# Switches_UI.net
KiCad netlist of a schematic drawn in Altium Designer
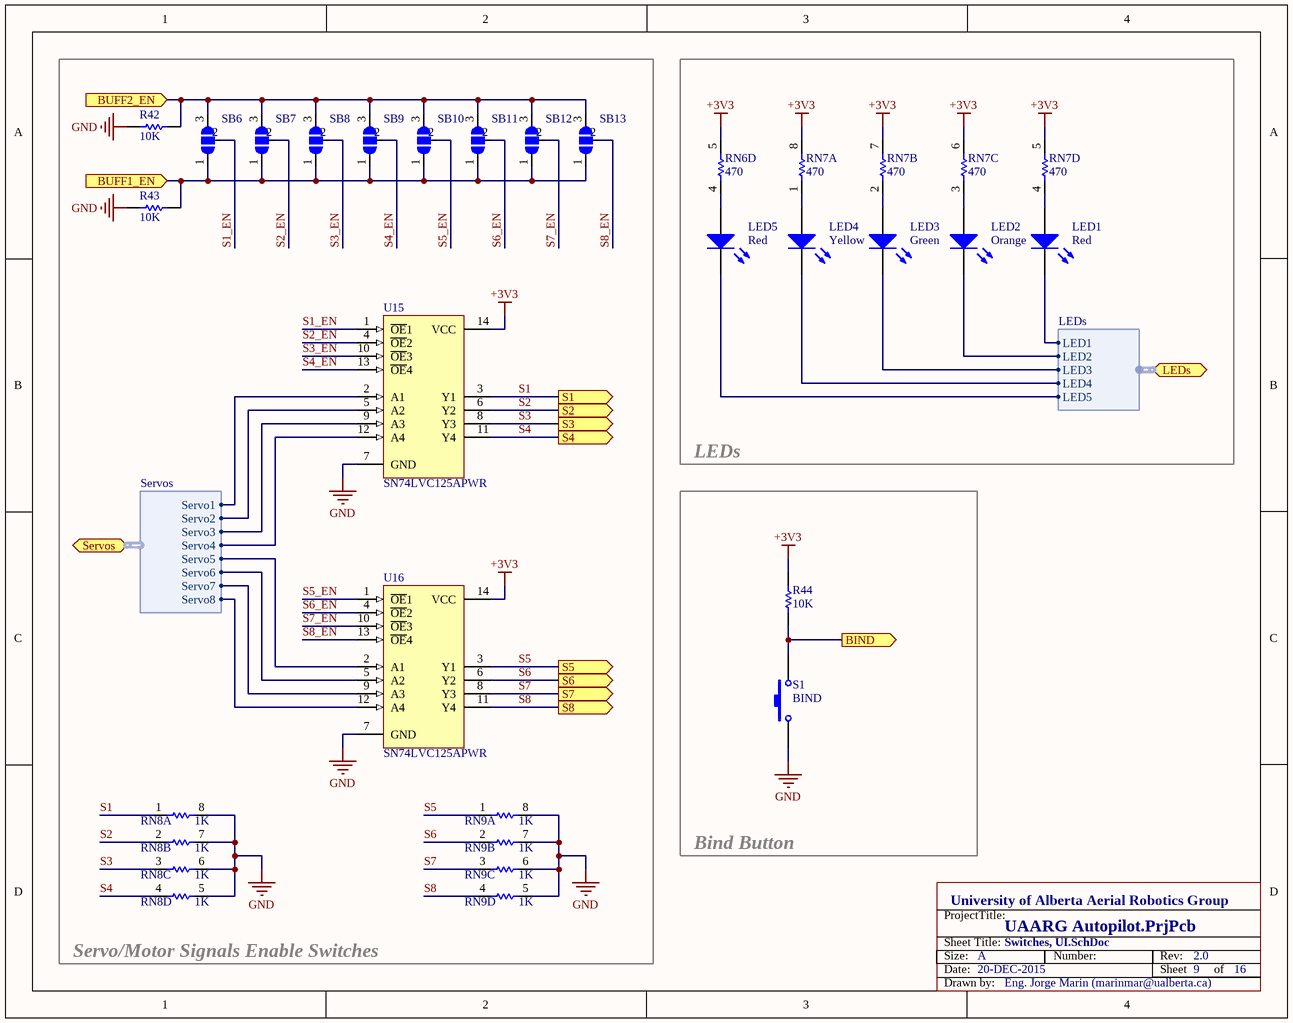
[diagram p0: Switches, UI.SchDoc]

(export (version "E")
  (design (tool "Eeschema 10.0.6"))
  (components
    (comp (ref "LED1")
      (value "LED")
      (footprint "LED_0603[1608M]")
      (description "LED RED CLEAR 0603 SMD")
      (fields
        (field (name "MANUFACTURER") "Lite-On Inc.")
        (field (name "MANUFACTURER PART NUMBER") "LTST-C190KRKT")
        (field (name "COLOR") "Red")
      )
      (libsource (lib "UAARG Autopilot") (part "LED"))
    )
    (comp (ref "LED2")
      (value "LED")
      (footprint "LED_0603[1608M]")
      (description "LED ORANGE CLEAR 0603 SMD")
      (fields
        (field (name "MANUFACTURER") "Lite-On Inc.")
        (field (name "MANUFACTURER PART NUMBER") "LTST-C190AKT")
        (field (name "COLOR") "Orange")
      )
      (libsource (lib "UAARG Autopilot") (part "LED"))
    )
    (comp (ref "LED3")
      (value "LED")
      (footprint "LED_0603[1608M]")
      (description "LED GREEN CLEAR 0603 SMD")
      (fields
        (field (name "MANUFACTURER") "Lite-On Inc.")
        (field (name "MANUFACTURER PART NUMBER") "LTST-C190KGKT")
        (field (name "COLOR") "Green")
      )
      (libsource (lib "UAARG Autopilot") (part "LED"))
    )
    (comp (ref "LED4")
      (value "LED")
      (footprint "LED_0603[1608M]")
      (description "LED YELLOW CLEAR 0603 SMD")
      (fields
        (field (name "MANUFACTURER") "Lite-On Inc.")
        (field (name "MANUFACTURER PART NUMBER") "LTST-C190YKT")
        (field (name "COLOR") "Yellow")
      )
      (libsource (lib "UAARG Autopilot") (part "LED"))
    )
    (comp (ref "LED5")
      (value "LED")
      (footprint "LED_0603[1608M]")
      (description "LED RED CLEAR 0603 SMD")
      (fields
        (field (name "MANUFACTURER") "Lite-On Inc.")
        (field (name "MANUFACTURER PART NUMBER") "LTST-C190KRKT")
        (field (name "COLOR") "Red")
      )
      (libsource (lib "UAARG Autopilot") (part "LED"))
    )
    (comp (ref "R42")
      (value "10K")
      (footprint "RES_0402[1005M]")
      (description "Resistor")
      (fields
        (field (name "MANUFACTURER") "Yageo")
        (field (name "MANUFACTURER PART NUMBER") "RC0402FR-0710KL")
      )
      (libsource (lib "UAARG Autopilot") (part "RES"))
    )
    (comp (ref "R43")
      (value "10K")
      (footprint "RES_0402[1005M]")
      (description "Resistor")
      (fields
        (field (name "MANUFACTURER") "Yageo")
        (field (name "MANUFACTURER PART NUMBER") "RC0402FR-0710KL")
      )
      (libsource (lib "UAARG Autopilot") (part "RES"))
    )
    (comp (ref "R44")
      (value "10K")
      (footprint "RES_0402[1005M]")
      (description "Resistor")
      (fields
        (field (name "MANUFACTURER") "Yageo")
        (field (name "MANUFACTURER PART NUMBER") "RC0402FR-0710KL")
      )
      (libsource (lib "UAARG Autopilot") (part "RES"))
    )
    (comp (ref "RN6")
      (value "470")
      (footprint "RES ARRAY SMD")
      (description "Isolated Resistor Network")
      (fields
        (field (name "MANUFACTURER") "Yageo")
        (field (name "MANUFACTURER PART NUMBER") "YC164-JR-07470RL")
      )
      (libsource (lib "UAARG Autopilot") (part "Res Network 1"))
    )
    (comp (ref "RN7")
      (value "470")
      (footprint "RES ARRAY SMD")
      (description "Isolated Resistor Network")
      (fields
        (field (name "MANUFACTURER") "Yageo")
        (field (name "MANUFACTURER PART NUMBER") "YC164-JR-07470RL")
      )
      (libsource (lib "UAARG Autopilot") (part "Res Network 1"))
    )
    (comp (ref "RN8")
      (value "1K")
      (footprint "RES ARRAY SMD")
      (description "Isolated Resistor Network")
      (fields
        (field (name "MANUFACTURER PART NUMBER") "YC164-JR-071KL")
        (field (name "MANUFACTURER") "Yageo")
      )
      (libsource (lib "UAARG Autopilot") (part "Res Network 1"))
    )
    (comp (ref "RN9")
      (value "1K")
      (footprint "RES ARRAY SMD")
      (description "Isolated Resistor Network")
      (fields
        (field (name "MANUFACTURER PART NUMBER") "YC164-JR-071KL")
        (field (name "MANUFACTURER") "Yageo")
      )
      (libsource (lib "UAARG Autopilot") (part "Res Network 1"))
    )
    (comp (ref "S1")
      (value "BIND")
      (footprint "SMD TACTILE SW KMR 2")
      (description "SWITCH TACTILE SPST-NO 0.05A 32V")
      (fields
        (field (name "MANUFACTURER PART NUMBER") "KMR221GLFS")
        (field (name "MANUFACTURER") "C&K Components")
      )
      (libsource (lib "Miscellaneous Devices") (part "SW-PB"))
    )
    (comp (ref "SB6")
      (value "SMD Jumper 1")
      (footprint "SMD JUMPER 1")
      (description "SMD Jumper 3 positions. Open")
      (libsource (lib "UAARG Autopilot") (part "SMD Jumper 1"))
    )
    (comp (ref "SB7")
      (value "SMD Jumper 1")
      (footprint "SMD JUMPER 1")
      (description "SMD Jumper 3 positions. Open")
      (libsource (lib "UAARG Autopilot") (part "SMD Jumper 1"))
    )
    (comp (ref "SB8")
      (value "SMD Jumper 1")
      (footprint "SMD JUMPER 1")
      (description "SMD Jumper 3 positions. Open")
      (libsource (lib "UAARG Autopilot") (part "SMD Jumper 1"))
    )
    (comp (ref "SB9")
      (value "SMD Jumper 1")
      (footprint "SMD JUMPER 1")
      (description "SMD Jumper 3 positions. Open")
      (libsource (lib "UAARG Autopilot") (part "SMD Jumper 1"))
    )
    (comp (ref "SB10")
      (value "SMD Jumper 1")
      (footprint "SMD JUMPER 1")
      (description "SMD Jumper 3 positions. Open")
      (libsource (lib "UAARG Autopilot") (part "SMD Jumper 1"))
    )
    (comp (ref "SB11")
      (value "SMD Jumper 1")
      (footprint "SMD JUMPER 1")
      (description "SMD Jumper 3 positions. Open")
      (libsource (lib "UAARG Autopilot") (part "SMD Jumper 1"))
    )
    (comp (ref "SB12")
      (value "SMD Jumper 1")
      (footprint "SMD JUMPER 1")
      (description "SMD Jumper 3 positions. Open")
      (libsource (lib "UAARG Autopilot") (part "SMD Jumper 1"))
    )
    (comp (ref "SB13")
      (value "SMD Jumper 1")
      (footprint "SMD JUMPER 1")
      (description "SMD Jumper 3 positions. Open")
      (libsource (lib "UAARG Autopilot") (part "SMD Jumper 1"))
    )
    (comp (ref "U15")
      (value "SN74LVC125APWR")
      (footprint "TSSOP-14")
      (fields (field (name "MANUFACTURER") "Texas Instruments"))
      (libsource (lib "FSC Logic Buffer Line Driver") (part "DM74LS125AM"))
    )
    (comp (ref "U16")
      (value "SN74LVC125APWR")
      (footprint "TSSOP-14")
      (fields (field (name "MANUFACTURER") "Texas Instruments"))
      (libsource (lib "FSC Logic Buffer Line Driver") (part "DM74LS125AM"))
    )
  )
  (nets
    (net (code "3") (name "+3V3") (class "Default")
      (node (ref "R44") (pin "2") (pinfunction "2_2") (pintype "passive"))
      (node (ref "RN6") (pin "5") (pinfunction "5_5") (pintype "passive"))
      (node (ref "RN7") (pin "5") (pinfunction "5_5") (pintype "passive"))
      (node (ref "RN7") (pin "6") (pinfunction "6_6") (pintype "passive"))
      (node (ref "RN7") (pin "7") (pinfunction "7_7") (pintype "passive"))
      (node (ref "RN7") (pin "8") (pinfunction "8_8") (pintype "passive"))
      (node (ref "U15") (pin "14") (pinfunction "VCC_14") (pintype "power_in"))
      (node (ref "U16") (pin "14") (pinfunction "VCC_14") (pintype "power_in"))
    )
    (net (code "4") (name "/BIND") (class "Default")
      (node (ref "R44") (pin "1") (pinfunction "1_1") (pintype "passive"))
      (node (ref "S1") (pin "2") (pinfunction "2_2") (pintype "passive"))
    )
    (net (code "5") (name "/BUFF1_EN") (class "Default")
      (node (ref "R43") (pin "1") (pinfunction "1_1") (pintype "passive"))
      (node (ref "SB10") (pin "1") (pinfunction "1_1") (pintype "passive"))
      (node (ref "SB11") (pin "1") (pinfunction "1_1") (pintype "passive"))
      (node (ref "SB12") (pin "1") (pinfunction "1_1") (pintype "passive"))
      (node (ref "SB13") (pin "1") (pinfunction "1_1") (pintype "passive"))
      (node (ref "SB6") (pin "1") (pinfunction "1_1") (pintype "passive"))
      (node (ref "SB7") (pin "1") (pinfunction "1_1") (pintype "passive"))
      (node (ref "SB8") (pin "1") (pinfunction "1_1") (pintype "passive"))
      (node (ref "SB9") (pin "1") (pinfunction "1_1") (pintype "passive"))
    )
    (net (code "6") (name "/BUFF2_EN") (class "Default")
      (node (ref "R42") (pin "1") (pinfunction "1_1") (pintype "passive"))
      (node (ref "SB10") (pin "3") (pinfunction "3_3") (pintype "passive"))
      (node (ref "SB11") (pin "3") (pinfunction "3_3") (pintype "passive"))
      (node (ref "SB12") (pin "3") (pinfunction "3_3") (pintype "passive"))
      (node (ref "SB13") (pin "3") (pinfunction "3_3") (pintype "passive"))
      (node (ref "SB6") (pin "3") (pinfunction "3_3") (pintype "passive"))
      (node (ref "SB7") (pin "3") (pinfunction "3_3") (pintype "passive"))
      (node (ref "SB8") (pin "3") (pinfunction "3_3") (pintype "passive"))
      (node (ref "SB9") (pin "3") (pinfunction "3_3") (pintype "passive"))
    )
    (net (code "7") (name "/LED1") (class "Default")
      (node (ref "LED1") (pin "2") (pinfunction "K_2") (pintype "passive"))
    )
    (net (code "8") (name "/LED2") (class "Default")
      (node (ref "LED2") (pin "2") (pinfunction "K_2") (pintype "passive"))
    )
    (net (code "9") (name "/LED3") (class "Default")
      (node (ref "LED3") (pin "2") (pinfunction "K_2") (pintype "passive"))
    )
    (net (code "10") (name "/LED4") (class "Default")
      (node (ref "LED4") (pin "2") (pinfunction "K_2") (pintype "passive"))
    )
    (net (code "11") (name "/LED5") (class "Default")
      (node (ref "LED5") (pin "2") (pinfunction "K_2") (pintype "passive"))
    )
    (net (code "12") (name "/S1") (class "Default")
      (node (ref "RN8") (pin "1") (pinfunction "1_1") (pintype "passive"))
      (node (ref "U15") (pin "3") (pinfunction "Y1_3") (pintype "tri_state"))
    )
    (net (code "13") (name "/S1_EN") (class "Default")
      (node (ref "SB6") (pin "2") (pinfunction "2_2") (pintype "passive"))
      (node (ref "U15") (pin "1") (pinfunction "~{OE}1_1") (pintype "input"))
    )
    (net (code "14") (name "/S2") (class "Default")
      (node (ref "RN8") (pin "2") (pinfunction "2_2") (pintype "passive"))
      (node (ref "U15") (pin "6") (pinfunction "Y2_6") (pintype "tri_state"))
    )
    (net (code "15") (name "/S2_EN") (class "Default")
      (node (ref "SB7") (pin "2") (pinfunction "2_2") (pintype "passive"))
      (node (ref "U15") (pin "4") (pinfunction "~{OE}2_4") (pintype "input"))
    )
    (net (code "16") (name "/S3") (class "Default")
      (node (ref "RN8") (pin "3") (pinfunction "3_3") (pintype "passive"))
      (node (ref "U15") (pin "8") (pinfunction "Y3_8") (pintype "tri_state"))
    )
    (net (code "17") (name "/S3_EN") (class "Default")
      (node (ref "SB8") (pin "2") (pinfunction "2_2") (pintype "passive"))
      (node (ref "U15") (pin "10") (pinfunction "~{OE}3_10") (pintype "input"))
    )
    (net (code "18") (name "/S4") (class "Default")
      (node (ref "RN8") (pin "4") (pinfunction "4_4") (pintype "passive"))
      (node (ref "U15") (pin "11") (pinfunction "Y4_11") (pintype "tri_state"))
    )
    (net (code "19") (name "/S4_EN") (class "Default")
      (node (ref "SB9") (pin "2") (pinfunction "2_2") (pintype "passive"))
      (node (ref "U15") (pin "13") (pinfunction "~{OE}4_13") (pintype "input"))
    )
    (net (code "20") (name "/S5") (class "Default")
      (node (ref "RN9") (pin "1") (pinfunction "1_1") (pintype "passive"))
      (node (ref "U16") (pin "3") (pinfunction "Y1_3") (pintype "tri_state"))
    )
    (net (code "21") (name "/S5_EN") (class "Default")
      (node (ref "SB10") (pin "2") (pinfunction "2_2") (pintype "passive"))
      (node (ref "U16") (pin "1") (pinfunction "~{OE}1_1") (pintype "input"))
    )
    (net (code "22") (name "/S6") (class "Default")
      (node (ref "RN9") (pin "2") (pinfunction "2_2") (pintype "passive"))
      (node (ref "U16") (pin "6") (pinfunction "Y2_6") (pintype "tri_state"))
    )
    (net (code "23") (name "/S6_EN") (class "Default")
      (node (ref "SB11") (pin "2") (pinfunction "2_2") (pintype "passive"))
      (node (ref "U16") (pin "4") (pinfunction "~{OE}2_4") (pintype "input"))
    )
    (net (code "24") (name "/S7") (class "Default")
      (node (ref "RN9") (pin "3") (pinfunction "3_3") (pintype "passive"))
      (node (ref "U16") (pin "8") (pinfunction "Y3_8") (pintype "tri_state"))
    )
    (net (code "25") (name "/S7_EN") (class "Default")
      (node (ref "SB12") (pin "2") (pinfunction "2_2") (pintype "passive"))
      (node (ref "U16") (pin "10") (pinfunction "~{OE}3_10") (pintype "input"))
    )
    (net (code "26") (name "/S8") (class "Default")
      (node (ref "RN9") (pin "4") (pinfunction "4_4") (pintype "passive"))
      (node (ref "U16") (pin "11") (pinfunction "Y4_11") (pintype "tri_state"))
    )
    (net (code "27") (name "/S8_EN") (class "Default")
      (node (ref "SB13") (pin "2") (pinfunction "2_2") (pintype "passive"))
      (node (ref "U16") (pin "13") (pinfunction "~{OE}4_13") (pintype "input"))
    )
    (net (code "28") (name "/Servo1") (class "Default")
      (node (ref "U15") (pin "2") (pinfunction "A1_2") (pintype "input"))
    )
    (net (code "29") (name "/Servo2") (class "Default")
      (node (ref "U15") (pin "5") (pinfunction "A2_5") (pintype "input"))
    )
    (net (code "30") (name "/Servo3") (class "Default")
      (node (ref "U15") (pin "9") (pinfunction "A3_9") (pintype "input"))
    )
    (net (code "31") (name "/Servo4") (class "Default")
      (node (ref "U15") (pin "12") (pinfunction "A4_12") (pintype "input"))
    )
    (net (code "32") (name "/Servo5") (class "Default")
      (node (ref "U16") (pin "2") (pinfunction "A1_2") (pintype "input"))
    )
    (net (code "33") (name "/Servo6") (class "Default")
      (node (ref "U16") (pin "5") (pinfunction "A2_5") (pintype "input"))
    )
    (net (code "34") (name "/Servo7") (class "Default")
      (node (ref "U16") (pin "9") (pinfunction "A3_9") (pintype "input"))
    )
    (net (code "35") (name "/Servo8") (class "Default")
      (node (ref "U16") (pin "12") (pinfunction "A4_12") (pintype "input"))
    )
    (net (code "38") (name "GND") (class "Default")
      (node (ref "R42") (pin "2") (pinfunction "2_2") (pintype "passive"))
      (node (ref "R43") (pin "2") (pinfunction "2_2") (pintype "passive"))
      (node (ref "RN8") (pin "5") (pinfunction "5_5") (pintype "passive"))
      (node (ref "RN8") (pin "6") (pinfunction "6_6") (pintype "passive"))
      (node (ref "RN8") (pin "7") (pinfunction "7_7") (pintype "passive"))
      (node (ref "RN8") (pin "8") (pinfunction "8_8") (pintype "passive"))
      (node (ref "RN9") (pin "5") (pinfunction "5_5") (pintype "passive"))
      (node (ref "RN9") (pin "6") (pinfunction "6_6") (pintype "passive"))
      (node (ref "RN9") (pin "7") (pinfunction "7_7") (pintype "passive"))
      (node (ref "RN9") (pin "8") (pinfunction "8_8") (pintype "passive"))
      (node (ref "S1") (pin "1") (pinfunction "1_1") (pintype "passive"))
      (node (ref "U15") (pin "7") (pinfunction "GND_7") (pintype "power_in"))
      (node (ref "U16") (pin "7") (pinfunction "GND_7") (pintype "power_in"))
    )
    (net (code "39") (name "Net-(LED1-A)") (class "Default")
      (node (ref "LED1") (pin "1") (pinfunction "A_1") (pintype "passive"))
      (node (ref "RN7") (pin "4") (pinfunction "4_4") (pintype "passive"))
    )
    (net (code "40") (name "Net-(LED2-A)") (class "Default")
      (node (ref "LED2") (pin "1") (pinfunction "A_1") (pintype "passive"))
      (node (ref "RN7") (pin "3") (pinfunction "3_3") (pintype "passive"))
    )
    (net (code "41") (name "Net-(LED3-A)") (class "Default")
      (node (ref "LED3") (pin "1") (pinfunction "A_1") (pintype "passive"))
      (node (ref "RN7") (pin "2") (pinfunction "2_2") (pintype "passive"))
    )
    (net (code "42") (name "Net-(LED4-A)") (class "Default")
      (node (ref "LED4") (pin "1") (pinfunction "A_1") (pintype "passive"))
      (node (ref "RN7") (pin "1") (pinfunction "1_1") (pintype "passive"))
    )
    (net (code "43") (name "Net-(LED5-A)") (class "Default")
      (node (ref "LED5") (pin "1") (pinfunction "A_1") (pintype "passive"))
      (node (ref "RN6") (pin "4") (pinfunction "4_4") (pintype "passive"))
    )
  )
)
